# PIXRACER-SERIALS-R12.net
KiCad netlist of a schematic drawn in Altium Designer
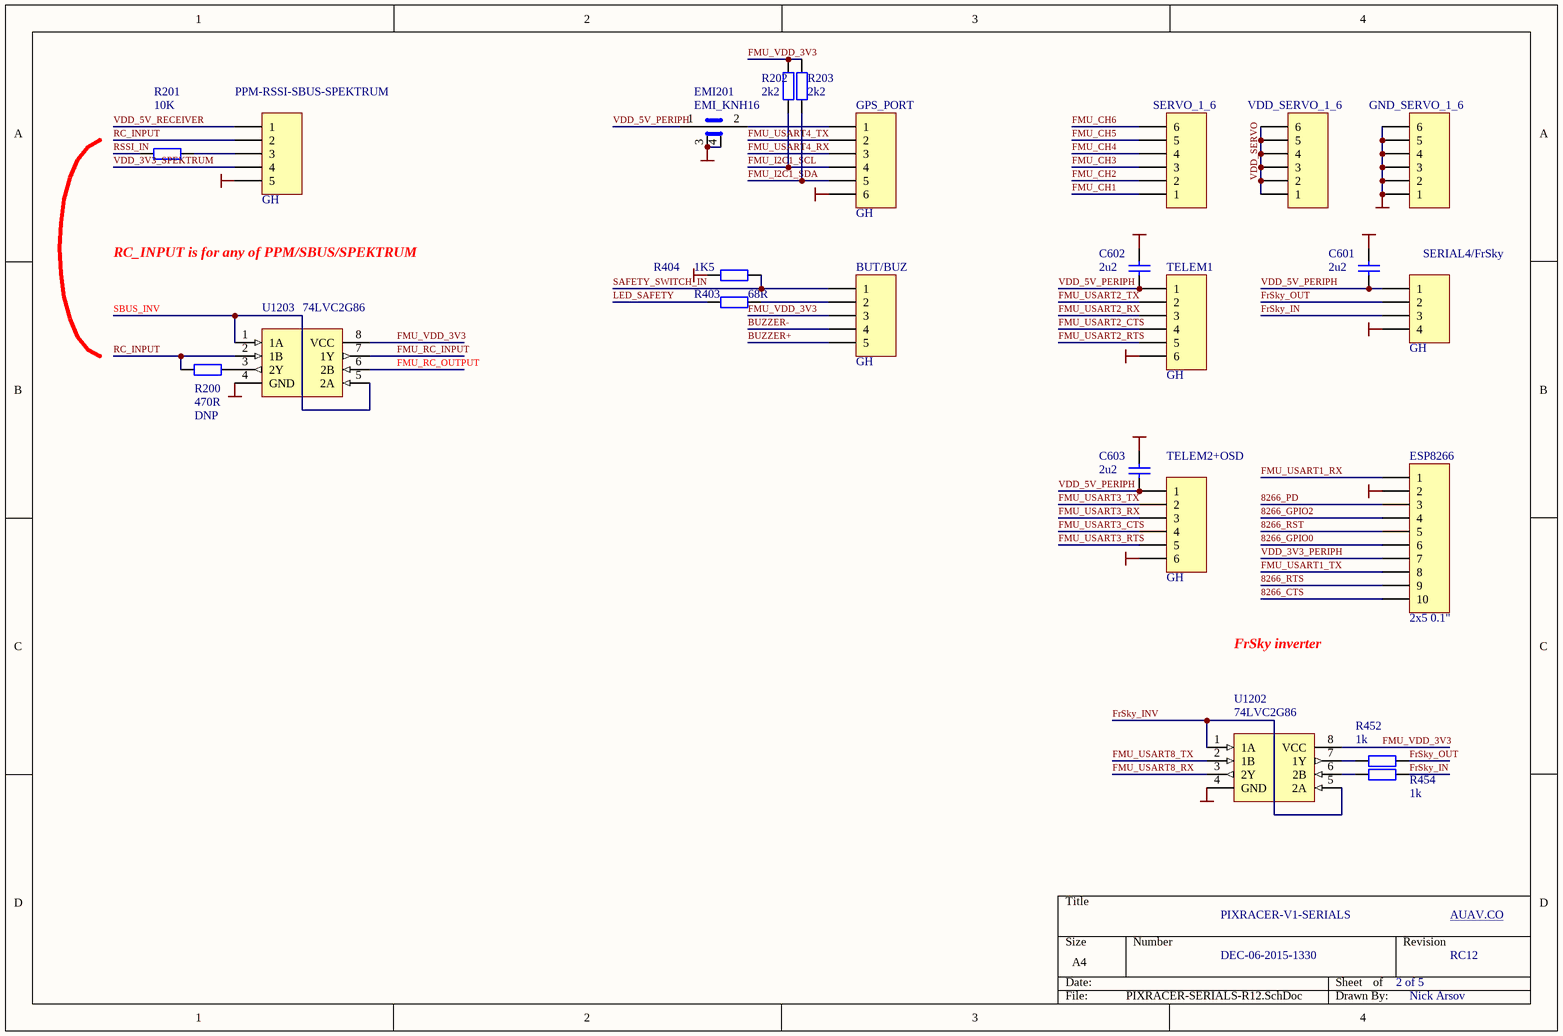
[diagram p0: PIXRACER-SERIALS-R12.SchDoc]

(export (version "E")
  (design (tool "Eeschema 10.0.6"))
  (components
    (comp (ref "BUT/BUZ")
      (value "GH")
      (footprint "Molex_Clik_1.25_5H")
      (description "Header, 5-Pin")
      (fields (field (name "PUBLISHER") "Altium Limited"))
      (libsource (lib "Miscellaneous Connectors") (part "Header 5"))
    )
    (comp (ref "C601")
      (value "2u2")
      (footprint "0402A")
      (description "Capacitor")
      (fields (field (name "PUBLISHER") "Altium Limited"))
      (libsource (lib "Miscellaneous Devices") (part "Cap"))
    )
    (comp (ref "C602")
      (value "2u2")
      (footprint "0402A")
      (description "Capacitor")
      (fields (field (name "PUBLISHER") "Altium Limited"))
      (libsource (lib "Miscellaneous Devices") (part "Cap"))
    )
    (comp (ref "C603")
      (value "2u2")
      (footprint "0402A")
      (description "Capacitor")
      (fields (field (name "PUBLISHER") "Altium Limited"))
      (libsource (lib "Miscellaneous Devices") (part "Cap"))
    )
    (comp (ref "EMI201")
      (value "EMI_KNH16")
      (footprint "EMI_KNH16_0603")
      (libsource (lib "My_Altium") (part "EMI_KNH16"))
    )
    (comp (ref "ESP8266")
      (value "2x5 0.1\"")
      (footprint "2.54mm_10pin_SMD")
      (description "Header, 10-Pin")
      (fields (field (name "PUBLISHER") "Altium Limited"))
      (libsource (lib "Miscellaneous Connectors") (part "Header 10"))
    )
    (comp (ref "GND_SERVO_1_6")
      (value "Header 6")
      (footprint "HDR1X6")
      (description "Header, 6-Pin")
      (fields (field (name "PUBLISHER") "Altium Limited"))
      (libsource (lib "") (part "Header 6_1"))
    )
    (comp (ref "GPS_PORT")
      (value "GH")
      (footprint "Molex_Clok_1.25_6H")
      (description "Header, 6-Pin")
      (fields (field (name "PUBLISHER") "Altium Limited"))
      (libsource (lib "Miscellaneous Connectors") (part "Header 6"))
    )
    (comp (ref "PPM-RSSI-SBUS-SPEKTRUM")
      (value "GH")
      (footprint "Molex_Clik_1.25_5H")
      (description "Header, 5-Pin")
      (fields (field (name "PUBLISHER") "Altium Limited"))
      (libsource (lib "Miscellaneous Connectors") (part "Header 5"))
    )
    (comp (ref "R200")
      (value "470R")
      (footprint "0402A")
      (description "Resistor")
      (fields (field (name "REM") "DNP") (field (name "PUBLISHER") "Altium Limited"))
      (libsource (lib "") (part "Res2_1"))
    )
    (comp (ref "R201")
      (value "10K")
      (footprint "0402A")
      (description "Resistor")
      (fields (field (name "PUBLISHER") "Altium Limited"))
      (libsource (lib "") (part "Res2_1"))
    )
    (comp (ref "R202")
      (value "2k2")
      (footprint "0402A")
      (description "Resistor")
      (fields (field (name "PUBLISHER") "Altium Limited"))
      (libsource (lib "Miscellaneous Devices") (part "Res2"))
    )
    (comp (ref "R203")
      (value "2k2")
      (footprint "0402A")
      (description "Resistor")
      (fields (field (name "PUBLISHER") "Altium Limited"))
      (libsource (lib "Miscellaneous Devices") (part "Res2"))
    )
    (comp (ref "R403")
      (value "68R")
      (footprint "0402A")
      (description "Resistor")
      (fields (field (name "PUBLISHER") "Altium Limited"))
      (libsource (lib "") (part "Res2_1"))
    )
    (comp (ref "R404")
      (value "1K5")
      (footprint "0402A")
      (description "Resistor")
      (fields (field (name "PUBLISHER") "Altium Limited"))
      (libsource (lib "") (part "Res2_1"))
    )
    (comp (ref "R452")
      (value "1k")
      (footprint "0402A")
      (description "Resistor")
      (fields (field (name "PUBLISHER") "Altium Limited"))
      (libsource (lib "") (part "Res2_1"))
    )
    (comp (ref "R454")
      (value "1k")
      (footprint "0402A")
      (description "Resistor")
      (fields (field (name "PUBLISHER") "Altium Limited"))
      (libsource (lib "") (part "Res2_1"))
    )
    (comp (ref "SERIAL4/FrSky")
      (value "GH")
      (footprint "Molex_1.25_click_4")
      (description "Header, 4-Pin")
      (fields (field (name "PUBLISHER") "Altium Limited"))
      (libsource (lib "Miscellaneous Connectors") (part "Header 4"))
    )
    (comp (ref "SERVO_1_6")
      (value "Header 6")
      (footprint "HDR1X6")
      (description "Header, 6-Pin")
      (fields (field (name "PUBLISHER") "Altium Limited"))
      (libsource (lib "") (part "Header 6_1"))
    )
    (comp (ref "TELEM1")
      (value "GH")
      (footprint "Molex_Clok_1.25_6H")
      (description "Header, 6-Pin")
      (fields (field (name "PUBLISHER") "Altium Limited"))
      (libsource (lib "Miscellaneous Connectors") (part "Header 6"))
    )
    (comp (ref "TELEM2+OSD")
      (value "GH")
      (footprint "Molex_Clok_1.25_6H")
      (description "Header, 6-Pin")
      (fields (field (name "PUBLISHER") "Altium Limited"))
      (libsource (lib "Miscellaneous Connectors") (part "Header 6"))
    )
    (comp (ref "U1202")
      (value "74LVC2G86")
      (footprint "DCU(SM-8)")
      (libsource (lib "My_Altium") (part "74LVC2G86"))
    )
    (comp (ref "U1203")
      (value "74LVC2G86")
      (footprint "DCU(SM-8)")
      (libsource (lib "My_Altium") (part "74LVC2G86"))
    )
    (comp (ref "VDD_SERVO_1_6")
      (value "Header 6")
      (footprint "HDR1X6")
      (description "Header, 6-Pin")
      (fields (field (name "PUBLISHER") "Altium Limited"))
      (libsource (lib "") (part "Header 6_1"))
    )
  )
  (nets
    (net (code "1") (name "/8266_CTS") (class "Default")
      (node (ref "ESP8266") (pin "10") (pinfunction "10_10") (pintype "passive"))
    )
    (net (code "2") (name "/8266_GPIO0") (class "Default")
      (node (ref "ESP8266") (pin "6") (pinfunction "6_6") (pintype "passive"))
    )
    (net (code "3") (name "/8266_GPIO2") (class "Default")
      (node (ref "ESP8266") (pin "4") (pinfunction "4_4") (pintype "passive"))
    )
    (net (code "4") (name "/8266_PD") (class "Default")
      (node (ref "ESP8266") (pin "3") (pinfunction "3_3") (pintype "passive"))
    )
    (net (code "5") (name "/8266_RST") (class "Default")
      (node (ref "ESP8266") (pin "5") (pinfunction "5_5") (pintype "passive"))
    )
    (net (code "6") (name "/8266_RTS") (class "Default")
      (node (ref "ESP8266") (pin "9") (pinfunction "9_9") (pintype "passive"))
    )
    (net (code "7") (name "/BUZZER+") (class "Default")
      (node (ref "BUT/BUZ") (pin "5") (pinfunction "5_5") (pintype "passive"))
    )
    (net (code "8") (name "/BUZZER-") (class "Default")
      (node (ref "BUT/BUZ") (pin "4") (pinfunction "4_4") (pintype "passive"))
    )
    (net (code "9") (name "/FMU_CH1") (class "Default")
      (node (ref "SERVO_1_6") (pin "1") (pinfunction "1_1") (pintype "passive"))
    )
    (net (code "10") (name "/FMU_CH2") (class "Default")
      (node (ref "SERVO_1_6") (pin "2") (pinfunction "2_2") (pintype "passive"))
    )
    (net (code "11") (name "/FMU_CH3") (class "Default")
      (node (ref "SERVO_1_6") (pin "3") (pinfunction "3_3") (pintype "passive"))
    )
    (net (code "12") (name "/FMU_CH4") (class "Default")
      (node (ref "SERVO_1_6") (pin "4") (pinfunction "4_4") (pintype "passive"))
    )
    (net (code "13") (name "/FMU_CH5") (class "Default")
      (node (ref "SERVO_1_6") (pin "5") (pinfunction "5_5") (pintype "passive"))
    )
    (net (code "14") (name "/FMU_CH6") (class "Default")
      (node (ref "SERVO_1_6") (pin "6") (pinfunction "6_6") (pintype "passive"))
    )
    (net (code "15") (name "/FMU_I2C1_SCL") (class "Default")
      (node (ref "GPS_PORT") (pin "4") (pinfunction "4_4") (pintype "passive"))
      (node (ref "R202") (pin "2") (pinfunction "2_2") (pintype "passive"))
    )
    (net (code "16") (name "/FMU_I2C1_SDA") (class "Default")
      (node (ref "GPS_PORT") (pin "5") (pinfunction "5_5") (pintype "passive"))
      (node (ref "R203") (pin "2") (pinfunction "2_2") (pintype "passive"))
    )
    (net (code "17") (name "/FMU_RC_INPUT") (class "Default")
      (node (ref "U1203") (pin "7") (pinfunction "1Y_7") (pintype "output"))
    )
    (net (code "18") (name "/FMU_RC_OUTPUT") (class "Default")
      (node (ref "U1203") (pin "6") (pinfunction "2B_6") (pintype "input"))
    )
    (net (code "19") (name "/FMU_USART1_RX") (class "Default")
      (node (ref "ESP8266") (pin "1") (pinfunction "1_1") (pintype "passive"))
    )
    (net (code "20") (name "/FMU_USART1_TX") (class "Default")
      (node (ref "ESP8266") (pin "8") (pinfunction "8_8") (pintype "passive"))
    )
    (net (code "21") (name "/FMU_USART2_CTS") (class "Default")
      (node (ref "TELEM1") (pin "4") (pinfunction "4_4") (pintype "passive"))
    )
    (net (code "22") (name "/FMU_USART2_RTS") (class "Default")
      (node (ref "TELEM1") (pin "5") (pinfunction "5_5") (pintype "passive"))
    )
    (net (code "23") (name "/FMU_USART2_RX") (class "Default")
      (node (ref "TELEM1") (pin "3") (pinfunction "3_3") (pintype "passive"))
    )
    (net (code "24") (name "/FMU_USART2_TX") (class "Default")
      (node (ref "TELEM1") (pin "2") (pinfunction "2_2") (pintype "passive"))
    )
    (net (code "25") (name "/FMU_USART3_CTS") (class "Default")
      (node (ref "TELEM2+OSD") (pin "4") (pinfunction "4_4") (pintype "passive"))
    )
    (net (code "26") (name "/FMU_USART3_RTS") (class "Default")
      (node (ref "TELEM2+OSD") (pin "5") (pinfunction "5_5") (pintype "passive"))
    )
    (net (code "27") (name "/FMU_USART3_RX") (class "Default")
      (node (ref "TELEM2+OSD") (pin "3") (pinfunction "3_3") (pintype "passive"))
    )
    (net (code "28") (name "/FMU_USART3_TX") (class "Default")
      (node (ref "TELEM2+OSD") (pin "2") (pinfunction "2_2") (pintype "passive"))
    )
    (net (code "29") (name "/FMU_USART4_RX") (class "Default")
      (node (ref "GPS_PORT") (pin "3") (pinfunction "3_3") (pintype "passive"))
    )
    (net (code "30") (name "/FMU_USART4_TX") (class "Default")
      (node (ref "GPS_PORT") (pin "2") (pinfunction "2_2") (pintype "passive"))
    )
    (net (code "31") (name "/FMU_USART8_RX") (class "Default")
      (node (ref "U1202") (pin "3") (pinfunction "2Y_3") (pintype "output"))
    )
    (net (code "32") (name "/FMU_USART8_TX") (class "Default")
      (node (ref "U1202") (pin "2") (pinfunction "1B_2") (pintype "input"))
    )
    (net (code "33") (name "/FMU_VDD_3V3") (class "Default")
      (node (ref "BUT/BUZ") (pin "3") (pinfunction "3_3") (pintype "passive"))
      (node (ref "R202") (pin "1") (pinfunction "1_1") (pintype "passive"))
      (node (ref "R203") (pin "1") (pinfunction "1_1") (pintype "passive"))
      (node (ref "U1202") (pin "8") (pinfunction "VCC_8") (pintype "passive"))
      (node (ref "U1203") (pin "8") (pinfunction "VCC_8") (pintype "passive"))
    )
    (net (code "34") (name "/FrSky_IN") (class "Default")
      (node (ref "R454") (pin "1") (pinfunction "1_1") (pintype "passive"))
      (node (ref "SERIAL4/FrSky") (pin "3") (pinfunction "3_3") (pintype "passive"))
    )
    (net (code "35") (name "/FrSky_INV") (class "Default")
      (node (ref "U1202") (pin "1") (pinfunction "1A_1") (pintype "input"))
      (node (ref "U1202") (pin "5") (pinfunction "2A_5") (pintype "input"))
    )
    (net (code "36") (name "/FrSky_OUT") (class "Default")
      (node (ref "R452") (pin "1") (pinfunction "1_1") (pintype "passive"))
      (node (ref "SERIAL4/FrSky") (pin "2") (pinfunction "2_2") (pintype "passive"))
    )
    (net (code "37") (name "/LED_SAFETY") (class "Default")
      (node (ref "R403") (pin "2") (pinfunction "2_2") (pintype "passive"))
    )
    (net (code "38") (name "/RC_INPUT") (class "Default")
      (node (ref "PPM-RSSI-SBUS-SPEKTRUM") (pin "2") (pinfunction "2_2") (pintype "passive"))
      (node (ref "R200") (pin "2") (pinfunction "2_2") (pintype "passive"))
      (node (ref "U1203") (pin "2") (pinfunction "1B_2") (pintype "input"))
    )
    (net (code "39") (name "/RSSI_IN") (class "Default")
      (node (ref "R201") (pin "2") (pinfunction "2_2") (pintype "passive"))
    )
    (net (code "40") (name "/SAFETY_SWITCH_IN") (class "Default")
      (node (ref "BUT/BUZ") (pin "1") (pinfunction "1_1") (pintype "passive"))
      (node (ref "R404") (pin "1") (pinfunction "1_1") (pintype "passive"))
    )
    (net (code "41") (name "/SBUS_INV") (class "Default")
      (node (ref "U1203") (pin "1") (pinfunction "1A_1") (pintype "input"))
      (node (ref "U1203") (pin "5") (pinfunction "2A_5") (pintype "input"))
    )
    (net (code "42") (name "/VDD_3V3_PERIPH") (class "Default")
      (node (ref "ESP8266") (pin "7") (pinfunction "7_7") (pintype "passive"))
    )
    (net (code "43") (name "/VDD_3V3_SPEKTRUM") (class "Default")
      (node (ref "PPM-RSSI-SBUS-SPEKTRUM") (pin "4") (pinfunction "4_4") (pintype "passive"))
    )
    (net (code "44") (name "/VDD_5V_PERIPH") (class "Default")
      (node (ref "C601") (pin "1") (pinfunction "1_1") (pintype "passive"))
      (node (ref "C602") (pin "1") (pinfunction "1_1") (pintype "passive"))
      (node (ref "C603") (pin "1") (pinfunction "1_1") (pintype "passive"))
      (node (ref "EMI201") (pin "1") (pinfunction "L1_1") (pintype "passive"))
      (node (ref "SERIAL4/FrSky") (pin "1") (pinfunction "1_1") (pintype "passive"))
      (node (ref "TELEM1") (pin "1") (pinfunction "1_1") (pintype "passive"))
      (node (ref "TELEM2+OSD") (pin "1") (pinfunction "1_1") (pintype "passive"))
    )
    (net (code "45") (name "/VDD_5V_RECEIVER") (class "Default")
      (node (ref "PPM-RSSI-SBUS-SPEKTRUM") (pin "1") (pinfunction "1_1") (pintype "passive"))
    )
    (net (code "46") (name "/VDD_SERVO") (class "Default")
      (node (ref "VDD_SERVO_1_6") (pin "1") (pinfunction "1_1") (pintype "passive"))
      (node (ref "VDD_SERVO_1_6") (pin "2") (pinfunction "2_2") (pintype "passive"))
      (node (ref "VDD_SERVO_1_6") (pin "3") (pinfunction "3_3") (pintype "passive"))
      (node (ref "VDD_SERVO_1_6") (pin "4") (pinfunction "4_4") (pintype "passive"))
      (node (ref "VDD_SERVO_1_6") (pin "5") (pinfunction "5_5") (pintype "passive"))
      (node (ref "VDD_SERVO_1_6") (pin "6") (pinfunction "6_6") (pintype "passive"))
    )
    (net (code "47") (name "GND") (class "Default")
      (node (ref "C601") (pin "2") (pinfunction "2_2") (pintype "passive"))
      (node (ref "C602") (pin "2") (pinfunction "2_2") (pintype "passive"))
      (node (ref "C603") (pin "2") (pinfunction "2_2") (pintype "passive"))
      (node (ref "EMI201") (pin "3") (pinfunction "G_3") (pintype "power_in"))
      (node (ref "EMI201") (pin "4") (pinfunction "G_4") (pintype "passive"))
      (node (ref "ESP8266") (pin "2") (pinfunction "2_2") (pintype "passive"))
      (node (ref "GND_SERVO_1_6") (pin "1") (pinfunction "1_1") (pintype "passive"))
      (node (ref "GND_SERVO_1_6") (pin "2") (pinfunction "2_2") (pintype "passive"))
      (node (ref "GND_SERVO_1_6") (pin "3") (pinfunction "3_3") (pintype "passive"))
      (node (ref "GND_SERVO_1_6") (pin "4") (pinfunction "4_4") (pintype "passive"))
      (node (ref "GND_SERVO_1_6") (pin "5") (pinfunction "5_5") (pintype "passive"))
      (node (ref "GND_SERVO_1_6") (pin "6") (pinfunction "6_6") (pintype "passive"))
      (node (ref "GPS_PORT") (pin "6") (pinfunction "6_6") (pintype "passive"))
      (node (ref "PPM-RSSI-SBUS-SPEKTRUM") (pin "5") (pinfunction "5_5") (pintype "passive"))
      (node (ref "R404") (pin "2") (pinfunction "2_2") (pintype "passive"))
      (node (ref "SERIAL4/FrSky") (pin "4") (pinfunction "4_4") (pintype "passive"))
      (node (ref "TELEM1") (pin "6") (pinfunction "6_6") (pintype "passive"))
      (node (ref "TELEM2+OSD") (pin "6") (pinfunction "6_6") (pintype "passive"))
      (node (ref "U1202") (pin "4") (pinfunction "GND_4") (pintype "passive"))
      (node (ref "U1203") (pin "4") (pinfunction "GND_4") (pintype "passive"))
    )
    (net (code "48") (name "Net-(BUT/BUZ-Pad2)") (class "Default")
      (node (ref "BUT/BUZ") (pin "2") (pinfunction "2_2") (pintype "passive"))
      (node (ref "R403") (pin "1") (pinfunction "1_1") (pintype "passive"))
    )
    (net (code "49") (name "Net-(EMI201-L2)") (class "Default")
      (node (ref "EMI201") (pin "2") (pinfunction "L2_2") (pintype "passive"))
      (node (ref "GPS_PORT") (pin "1") (pinfunction "1_1") (pintype "passive"))
    )
    (net (code "50") (name "Net-(PPM-RSSI-SBUS-SPEKTRUM-Pad3)") (class "Default")
      (node (ref "PPM-RSSI-SBUS-SPEKTRUM") (pin "3") (pinfunction "3_3") (pintype "passive"))
      (node (ref "R201") (pin "1") (pinfunction "1_1") (pintype "passive"))
    )
    (net (code "51") (name "Net-(U1202-1Y)") (class "Default")
      (node (ref "R452") (pin "2") (pinfunction "2_2") (pintype "passive"))
      (node (ref "U1202") (pin "7") (pinfunction "1Y_7") (pintype "output"))
    )
    (net (code "52") (name "Net-(U1202-2B)") (class "Default")
      (node (ref "R454") (pin "2") (pinfunction "2_2") (pintype "passive"))
      (node (ref "U1202") (pin "6") (pinfunction "2B_6") (pintype "input"))
    )
    (net (code "53") (name "Net-(U1203-2Y)") (class "Default")
      (node (ref "R200") (pin "1") (pinfunction "1_1") (pintype "passive"))
      (node (ref "U1203") (pin "3") (pinfunction "2Y_3") (pintype "output"))
    )
  )
)
